# CarACESP32_2.net
KiCad netlist of a schematic drawn in Altium Designer
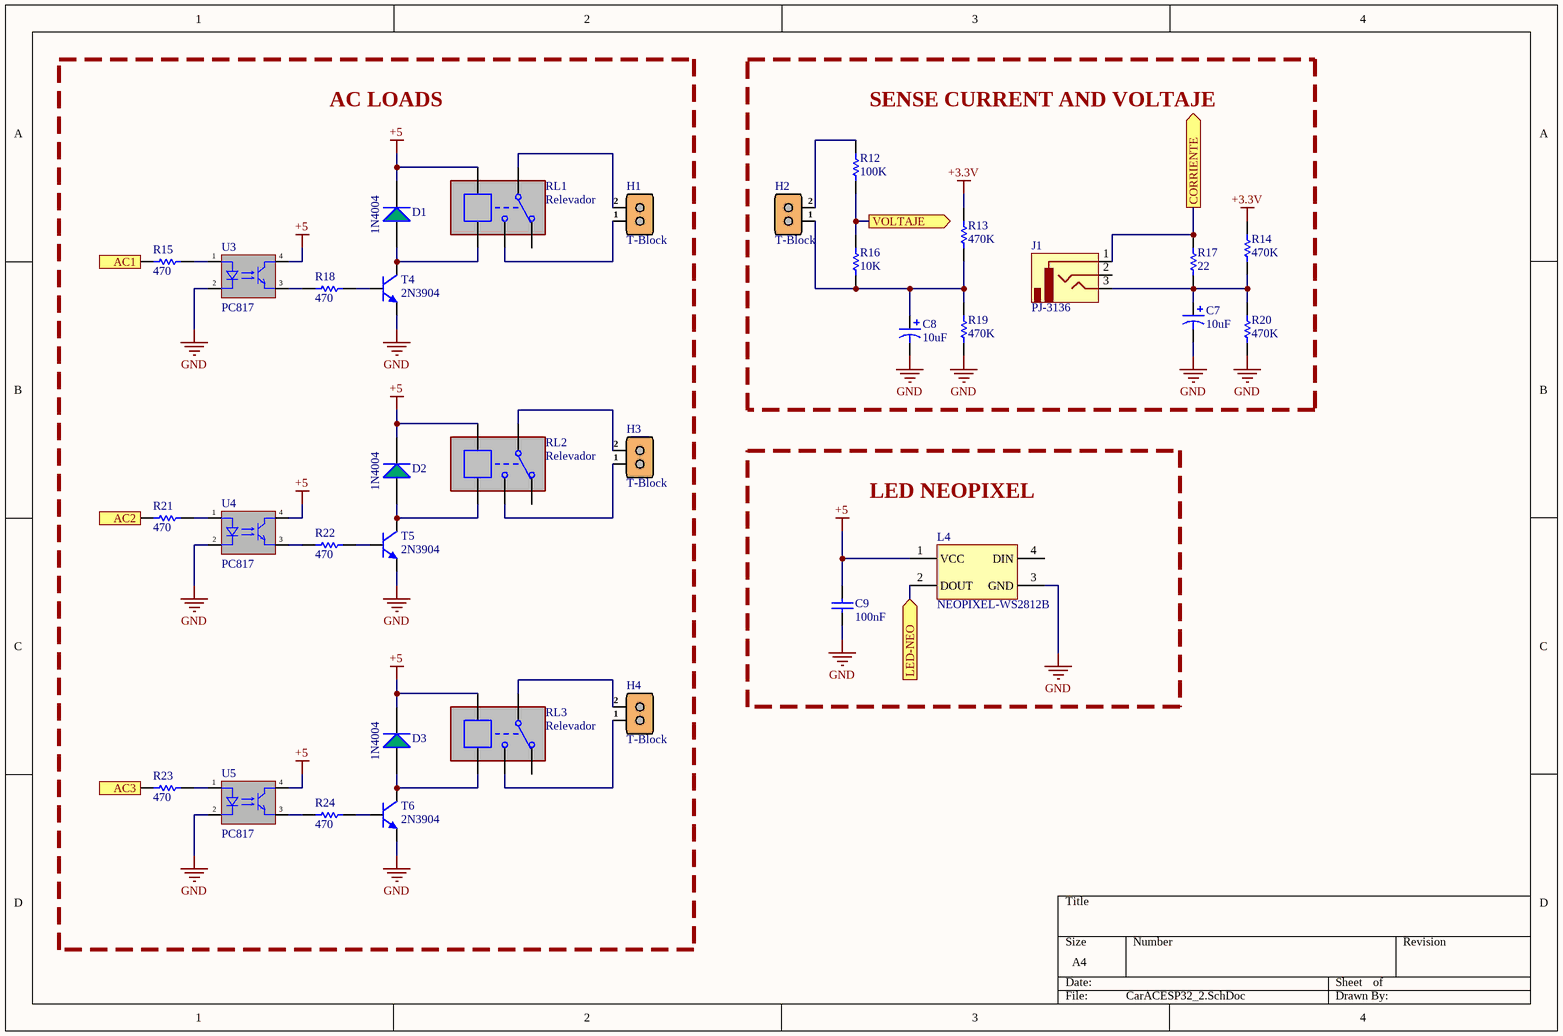
[diagram p0: CarACESP32_2.SchDoc]

(export (version "E")
  (design (tool "Eeschema 10.0.6"))
  (components
    (comp (ref "C7") (value "10uF") (footprint "100uF") (libsource (lib "MyLabrary") (part "CAP-ELEC-100uF")))
    (comp (ref "C8") (value "10uF") (footprint "100uF") (libsource (lib "MyLabrary") (part "CAP-ELEC-100uF")))
    (comp (ref "C9")
      (value "100nF")
      (footprint "Capacitor 1206")
      (description "Capacitor cerámico 1206 SMD")
      (libsource (lib "Mi Libreria") (part "Capacitor 1206"))
    )
    (comp (ref "D1")
      (value "1N4004")
      (footprint "1N4007 SMD")
      (description "Diodo Rectificador")
      (libsource (lib "Mi Libreria") (part "1N4007 SMD"))
    )
    (comp (ref "D2")
      (value "1N4004")
      (footprint "1N4007 SMD")
      (description "Diodo Rectificador")
      (libsource (lib "Mi Libreria") (part "1N4007 SMD"))
    )
    (comp (ref "D3")
      (value "1N4004")
      (footprint "1N4007 SMD")
      (description "Diodo Rectificador")
      (libsource (lib "Mi Libreria") (part "1N4007 SMD"))
    )
    (comp (ref "H1")
      (value "T-Block")
      (footprint "TBLOCK-2ORANGE")
      (description "Terminal de Bloque 2P 5.08mm")
      (libsource (lib "MyLabrary") (part "T-Block 5.08mm 2P"))
    )
    (comp (ref "H2")
      (value "T-Block")
      (footprint "TBLOCK-2ORANGE")
      (description "Terminal de Bloque 2P 5.08mm")
      (libsource (lib "MyLabrary") (part "T-Block 5.08mm 2P"))
    )
    (comp (ref "H3")
      (value "T-Block")
      (footprint "TBLOCK-2ORANGE")
      (description "Terminal de Bloque 2P 5.08mm")
      (libsource (lib "MyLabrary") (part "T-Block 5.08mm 2P"))
    )
    (comp (ref "H4")
      (value "T-Block")
      (footprint "TBLOCK-2ORANGE")
      (description "Terminal de Bloque 2P 5.08mm")
      (libsource (lib "MyLabrary") (part "T-Block 5.08mm 2P"))
    )
    (comp (ref "J1")
      (value "PJ-3136")
      (footprint "PJ-3136-X")
      (description "PJ-3136 Jack De Audio Hembra")
      (libsource (lib "MyLabrary") (part "JACK HEMBRA 3.5MM"))
    )
    (comp (ref "L4")
      (value "NEOPIXEL-WS2812B")
      (footprint "WS2812B")
      (description "LED NEOPIXEL WS2812B")
      (libsource (lib "MyLabrary") (part "NEOPIXEL-WS2812B"))
    )
    (comp (ref "R12")
      (value "100K")
      (footprint "Resistencia 1206")
      (description "Resistencia SMD 1206")
      (libsource (lib "Mi Libreria") (part "Resistencia SMD 1206"))
    )
    (comp (ref "R13")
      (value "470K")
      (footprint "Resistencia 1206")
      (description "Resistencia SMD 1206")
      (libsource (lib "Mi Libreria") (part "Resistencia SMD 1206"))
    )
    (comp (ref "R14")
      (value "470K")
      (footprint "Resistencia 1206")
      (description "Resistencia SMD 1206")
      (libsource (lib "Mi Libreria") (part "Resistencia SMD 1206"))
    )
    (comp (ref "R15")
      (value "470")
      (footprint "Resistencia 1206")
      (description "Resistencia SMD 1206")
      (libsource (lib "Mi Libreria") (part "Resistencia SMD 1206"))
    )
    (comp (ref "R16")
      (value "10K")
      (footprint "Resistencia 1206")
      (description "Resistencia SMD 1206")
      (libsource (lib "Mi Libreria") (part "Resistencia SMD 1206"))
    )
    (comp (ref "R17")
      (value "22")
      (footprint "Resistencia 1206")
      (description "Resistencia SMD 1206")
      (libsource (lib "Mi Libreria") (part "Resistencia SMD 1206"))
    )
    (comp (ref "R18")
      (value "470")
      (footprint "Resistencia 1206")
      (description "Resistencia SMD 1206")
      (libsource (lib "Mi Libreria") (part "Resistencia SMD 1206"))
    )
    (comp (ref "R19")
      (value "470K")
      (footprint "Resistencia 1206")
      (description "Resistencia SMD 1206")
      (libsource (lib "Mi Libreria") (part "Resistencia SMD 1206"))
    )
    (comp (ref "R20")
      (value "470K")
      (footprint "Resistencia 1206")
      (description "Resistencia SMD 1206")
      (libsource (lib "Mi Libreria") (part "Resistencia SMD 1206"))
    )
    (comp (ref "R21")
      (value "470")
      (footprint "Resistencia 1206")
      (description "Resistencia SMD 1206")
      (libsource (lib "Mi Libreria") (part "Resistencia SMD 1206"))
    )
    (comp (ref "R22")
      (value "470")
      (footprint "Resistencia 1206")
      (description "Resistencia SMD 1206")
      (libsource (lib "Mi Libreria") (part "Resistencia SMD 1206"))
    )
    (comp (ref "R23")
      (value "470")
      (footprint "Resistencia 1206")
      (description "Resistencia SMD 1206")
      (libsource (lib "Mi Libreria") (part "Resistencia SMD 1206"))
    )
    (comp (ref "R24")
      (value "470")
      (footprint "Resistencia 1206")
      (description "Resistencia SMD 1206")
      (libsource (lib "Mi Libreria") (part "Resistencia SMD 1206"))
    )
    (comp (ref "RL1")
      (value "Relevador")
      (footprint "Relevador Mini 20A")
      (description "Relevador Mini")
      (libsource (lib "Switch & Relays FAE") (part "Relevador S 5V 20A"))
    )
    (comp (ref "RL2")
      (value "Relevador")
      (footprint "Relevador Mini 20A")
      (description "Relevador Mini")
      (libsource (lib "Switch & Relays FAE") (part "Relevador S 5V 20A"))
    )
    (comp (ref "RL3")
      (value "Relevador")
      (footprint "Relevador Mini 20A")
      (description "Relevador Mini")
      (libsource (lib "Switch & Relays FAE") (part "Relevador S 5V 20A"))
    )
    (comp (ref "T4") (value "2N3904") (footprint "SOT23_M") (libsource (lib "MyLabrary") (part "MMBT2N3904")))
    (comp (ref "T5") (value "2N3904") (footprint "SOT23_M") (libsource (lib "MyLabrary") (part "MMBT2N3904")))
    (comp (ref "T6") (value "2N3904") (footprint "SOT23_M") (libsource (lib "MyLabrary") (part "MMBT2N3904")))
    (comp (ref "U3")
      (value "PC817")
      (footprint "PC817")
      (description "Optoacoplador NPN")
      (libsource (lib "Mi Libreria") (part "PC817"))
    )
    (comp (ref "U4")
      (value "PC817")
      (footprint "PC817")
      (description "Optoacoplador NPN")
      (libsource (lib "Mi Libreria") (part "PC817"))
    )
    (comp (ref "U5")
      (value "PC817")
      (footprint "PC817")
      (description "Optoacoplador NPN")
      (libsource (lib "Mi Libreria") (part "PC817"))
    )
  )
  (nets
    (net (code "1") (name "+3.3V") (class "Default")
      (node (ref "R13") (pin "2") (pinfunction "B_2") (pintype "passive"))
      (node (ref "R14") (pin "2") (pinfunction "B_2") (pintype "passive"))
    )
    (net (code "2") (name "+5") (class "Default")
      (node (ref "C9") (pin "2") (pinfunction "2_2") (pintype "passive"))
      (node (ref "D1") (pin "2") (pinfunction "C_2") (pintype "passive"))
      (node (ref "D2") (pin "2") (pinfunction "C_2") (pintype "passive"))
      (node (ref "D3") (pin "2") (pinfunction "C_2") (pintype "passive"))
      (node (ref "L4") (pin "1") (pinfunction "VCC_1") (pintype "passive"))
      (node (ref "RL1") (pin "1") (pinfunction "1_1") (pintype "passive"))
      (node (ref "RL2") (pin "1") (pinfunction "1_1") (pintype "passive"))
      (node (ref "RL3") (pin "1") (pinfunction "1_1") (pintype "passive"))
      (node (ref "U3") (pin "4") (pinfunction "C_4") (pintype "passive"))
      (node (ref "U4") (pin "4") (pinfunction "C_4") (pintype "passive"))
      (node (ref "U5") (pin "4") (pinfunction "C_4") (pintype "passive"))
    )
    (net (code "3") (name "/AC1") (class "Default")
      (node (ref "R15") (pin "2") (pinfunction "B_2") (pintype "passive"))
    )
    (net (code "4") (name "/AC2") (class "Default")
      (node (ref "R21") (pin "2") (pinfunction "B_2") (pintype "passive"))
    )
    (net (code "5") (name "/AC3") (class "Default")
      (node (ref "R23") (pin "2") (pinfunction "B_2") (pintype "passive"))
    )
    (net (code "6") (name "/CORRIENTE") (class "Default")
      (node (ref "J1") (pin "1") (pinfunction "1_1") (pintype "passive"))
      (node (ref "R17") (pin "2") (pinfunction "B_2") (pintype "passive"))
    )
    (net (code "7") (name "/LED-NEO") (class "Default")
      (node (ref "L4") (pin "2") (pinfunction "DOUT_2") (pintype "passive"))
    )
    (net (code "8") (name "/VOLTAJE") (class "Default")
      (node (ref "R12") (pin "1") (pinfunction "A_1") (pintype "passive"))
      (node (ref "R16") (pin "2") (pinfunction "B_2") (pintype "passive"))
    )
    (net (code "9") (name "GND") (class "Default")
      (node (ref "C7") (pin "2") (pinfunction "2_2") (pintype "passive"))
      (node (ref "C8") (pin "2") (pinfunction "2_2") (pintype "passive"))
      (node (ref "C9") (pin "1") (pinfunction "1_1") (pintype "passive"))
      (node (ref "L4") (pin "3") (pinfunction "GND_3") (pintype "passive"))
      (node (ref "R19") (pin "1") (pinfunction "A_1") (pintype "passive"))
      (node (ref "R20") (pin "1") (pinfunction "A_1") (pintype "passive"))
      (node (ref "T4") (pin "2") (pinfunction "E_2") (pintype "passive"))
      (node (ref "T5") (pin "2") (pinfunction "E_2") (pintype "passive"))
      (node (ref "T6") (pin "2") (pinfunction "E_2") (pintype "passive"))
      (node (ref "U3") (pin "2") (pinfunction "K_2") (pintype "passive"))
      (node (ref "U4") (pin "2") (pinfunction "K_2") (pintype "passive"))
      (node (ref "U5") (pin "2") (pinfunction "K_2") (pintype "passive"))
    )
    (net (code "10") (name "Net-(D1-A)") (class "Default")
      (node (ref "D1") (pin "1") (pinfunction "A_1") (pintype "passive"))
      (node (ref "RL1") (pin "2") (pinfunction "2_2") (pintype "passive"))
      (node (ref "T4") (pin "3") (pinfunction "C_3") (pintype "passive"))
    )
    (net (code "11") (name "Net-(D2-A)") (class "Default")
      (node (ref "D2") (pin "1") (pinfunction "A_1") (pintype "passive"))
      (node (ref "RL2") (pin "2") (pinfunction "2_2") (pintype "passive"))
      (node (ref "T5") (pin "3") (pinfunction "C_3") (pintype "passive"))
    )
    (net (code "12") (name "Net-(D3-A)") (class "Default")
      (node (ref "D3") (pin "1") (pinfunction "A_1") (pintype "passive"))
      (node (ref "RL3") (pin "2") (pinfunction "2_2") (pintype "passive"))
      (node (ref "T6") (pin "3") (pinfunction "C_3") (pintype "passive"))
    )
    (net (code "13") (name "Net-(H1-Pad1)") (class "Default")
      (node (ref "H1") (pin "1") (pinfunction "1_1") (pintype "passive"))
      (node (ref "RL1") (pin "4") (pinfunction "4_4") (pintype "passive"))
    )
    (net (code "14") (name "Net-(H1-Pad2)") (class "Default")
      (node (ref "H1") (pin "2") (pinfunction "2_2") (pintype "passive"))
      (node (ref "RL1") (pin "3") (pinfunction "3_3") (pintype "passive"))
    )
    (net (code "15") (name "Net-(H3-Pad1)") (class "Default")
      (node (ref "H3") (pin "1") (pinfunction "1_1") (pintype "passive"))
      (node (ref "RL2") (pin "4") (pinfunction "4_4") (pintype "passive"))
    )
    (net (code "16") (name "Net-(H3-Pad2)") (class "Default")
      (node (ref "H3") (pin "2") (pinfunction "2_2") (pintype "passive"))
      (node (ref "RL2") (pin "3") (pinfunction "3_3") (pintype "passive"))
    )
    (net (code "17") (name "Net-(H4-Pad1)") (class "Default")
      (node (ref "H4") (pin "1") (pinfunction "1_1") (pintype "passive"))
      (node (ref "RL3") (pin "4") (pinfunction "4_4") (pintype "passive"))
    )
    (net (code "18") (name "Net-(H4-Pad2)") (class "Default")
      (node (ref "H4") (pin "2") (pinfunction "2_2") (pintype "passive"))
      (node (ref "RL3") (pin "3") (pinfunction "3_3") (pintype "passive"))
    )
    (net (code "19") (name "Net-(R12-B)") (class "Default")
      (node (ref "H2") (pin "2") (pinfunction "2_2") (pintype "passive"))
      (node (ref "R12") (pin "2") (pinfunction "B_2") (pintype "passive"))
    )
    (net (code "20") (name "Net-(R13-A)") (class "Default")
      (node (ref "C8") (pin "1") (pinfunction "1_1") (pintype "passive"))
      (node (ref "H2") (pin "1") (pinfunction "1_1") (pintype "passive"))
      (node (ref "R13") (pin "1") (pinfunction "A_1") (pintype "passive"))
      (node (ref "R16") (pin "1") (pinfunction "A_1") (pintype "passive"))
      (node (ref "R19") (pin "2") (pinfunction "B_2") (pintype "passive"))
    )
    (net (code "21") (name "Net-(R14-A)") (class "Default")
      (node (ref "C7") (pin "1") (pinfunction "1_1") (pintype "passive"))
      (node (ref "J1") (pin "3") (pinfunction "3_3") (pintype "passive"))
      (node (ref "R14") (pin "1") (pinfunction "A_1") (pintype "passive"))
      (node (ref "R17") (pin "1") (pinfunction "A_1") (pintype "passive"))
      (node (ref "R20") (pin "2") (pinfunction "B_2") (pintype "passive"))
    )
    (net (code "22") (name "Net-(R15-A)") (class "Default")
      (node (ref "R15") (pin "1") (pinfunction "A_1") (pintype "passive"))
      (node (ref "U3") (pin "1") (pinfunction "A_1") (pintype "passive"))
    )
    (net (code "23") (name "Net-(R18-A)") (class "Default")
      (node (ref "R18") (pin "1") (pinfunction "A_1") (pintype "passive"))
      (node (ref "T4") (pin "1") (pinfunction "B_1") (pintype "passive"))
    )
    (net (code "24") (name "Net-(R18-B)") (class "Default")
      (node (ref "R18") (pin "2") (pinfunction "B_2") (pintype "passive"))
      (node (ref "U3") (pin "3") (pinfunction "E_3") (pintype "passive"))
    )
    (net (code "25") (name "Net-(R21-A)") (class "Default")
      (node (ref "R21") (pin "1") (pinfunction "A_1") (pintype "passive"))
      (node (ref "U4") (pin "1") (pinfunction "A_1") (pintype "passive"))
    )
    (net (code "26") (name "Net-(R22-A)") (class "Default")
      (node (ref "R22") (pin "1") (pinfunction "A_1") (pintype "passive"))
      (node (ref "T5") (pin "1") (pinfunction "B_1") (pintype "passive"))
    )
    (net (code "27") (name "Net-(R22-B)") (class "Default")
      (node (ref "R22") (pin "2") (pinfunction "B_2") (pintype "passive"))
      (node (ref "U4") (pin "3") (pinfunction "E_3") (pintype "passive"))
    )
    (net (code "28") (name "Net-(R23-A)") (class "Default")
      (node (ref "R23") (pin "1") (pinfunction "A_1") (pintype "passive"))
      (node (ref "U5") (pin "1") (pinfunction "A_1") (pintype "passive"))
    )
    (net (code "29") (name "Net-(R24-A)") (class "Default")
      (node (ref "R24") (pin "1") (pinfunction "A_1") (pintype "passive"))
      (node (ref "T6") (pin "1") (pinfunction "B_1") (pintype "passive"))
    )
    (net (code "30") (name "Net-(R24-B)") (class "Default")
      (node (ref "R24") (pin "2") (pinfunction "B_2") (pintype "passive"))
      (node (ref "U5") (pin "3") (pinfunction "E_3") (pintype "passive"))
    )
    (net (code "31") (name "unconnected-(J1-Pad2)") (class "Default")
      (node (ref "J1") (pin "2") (pinfunction "2_2") (pintype "passive"))
    )
    (net (code "32") (name "unconnected-(L4-DIN-Pad4)") (class "Default")
      (node (ref "L4") (pin "4") (pinfunction "DIN_4") (pintype "passive"))
    )
    (net (code "33") (name "unconnected-(RL1-Pad5)") (class "Default")
      (node (ref "RL1") (pin "5") (pinfunction "5_5") (pintype "passive"))
    )
    (net (code "34") (name "unconnected-(RL2-Pad5)") (class "Default")
      (node (ref "RL2") (pin "5") (pinfunction "5_5") (pintype "passive"))
    )
    (net (code "35") (name "unconnected-(RL3-Pad5)") (class "Default")
      (node (ref "RL3") (pin "5") (pinfunction "5_5") (pintype "passive"))
    )
  )
)
